# 01_-_LED_DRIVER.net
KiCad netlist of a schematic drawn in Altium Designer
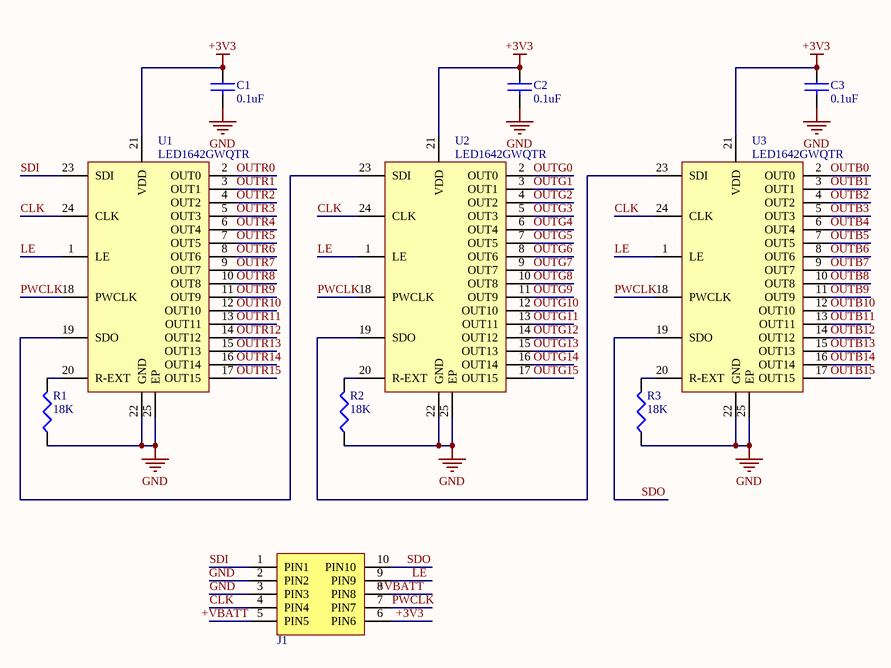
[diagram p0: [01] - LED DRIVER.SchDoc]

(export (version "E")
  (design (tool "Eeschema 10.0.6"))
  (components
    (comp (ref "C1")
      (value "0.1uF")
      (footprint "C0402")
      (description "Cap Ceramic 0.1uF 16V X7R 10% SMD 0402 125C C/T")
      (fields (field (name "TOLERANCE") "10%") (field (name "VOLTAGE") "16V"))
      (libsource (lib "Moon_Lamp_LED_Driver") (part "CL05B104KO5NNNC"))
    )
    (comp (ref "C2")
      (value "0.1uF")
      (footprint "C0402")
      (description "Cap Ceramic 0.1uF 16V X7R 10% SMD 0402 125C C/T")
      (fields (field (name "TOLERANCE") "10%") (field (name "VOLTAGE") "16V"))
      (libsource (lib "Moon_Lamp_LED_Driver") (part "CL05B104KO5NNNC"))
    )
    (comp (ref "C3")
      (value "0.1uF")
      (footprint "C0402")
      (description "Cap Ceramic 0.1uF 16V X7R 10% SMD 0402 125C C/T")
      (fields (field (name "TOLERANCE") "10%") (field (name "VOLTAGE") "16V"))
      (libsource (lib "Moon_Lamp_LED_Driver") (part "CL05B104KO5NNNC"))
    )
    (comp (ref "J1")
      (value "20021121-00010C4LF")
      (footprint "20021121-00010C4LF")
      (description "CONN HEADER SMD 10POS 1.27MM")
      (fields (field (name "MANUFACTURER") "Amphenol FCI"))
      (libsource (lib "Moon_Lamp_LED_Driver") (part "20021121-00010C4LF"))
    )
    (comp (ref "R1")
      (value "18K")
      (footprint "R0402")
      (fields
        (field (name "MANUFACTURER") "TE Connectivity")
        (field (name "MANUFACTURER PART NUMBER") "CRGCQ0402F18K")
      )
      (libsource (lib "Moon_Lamp_LED_Driver") (part "CRGCQ0402F18K"))
    )
    (comp (ref "R2")
      (value "18K")
      (footprint "R0402")
      (fields
        (field (name "MANUFACTURER") "TE Connectivity")
        (field (name "MANUFACTURER PART NUMBER") "CRGCQ0402F18K")
      )
      (libsource (lib "Moon_Lamp_LED_Driver") (part "CRGCQ0402F18K"))
    )
    (comp (ref "R3")
      (value "18K")
      (footprint "R0402")
      (fields
        (field (name "MANUFACTURER") "TE Connectivity")
        (field (name "MANUFACTURER PART NUMBER") "CRGCQ0402F18K")
      )
      (libsource (lib "Moon_Lamp_LED_Driver") (part "CRGCQ0402F18K"))
    )
    (comp (ref "U1")
      (value "LED1642GWQTR")
      (footprint "QFN24")
      (description "IC LED DRIVER LIN DIM 40MA 24QFN")
      (fields (field (name "MANUFACTURER") "STMicroelectronics"))
      (libsource (lib "Moon_Lamp_LED_Driver") (part "LED1642GWQTR"))
    )
    (comp (ref "U2")
      (value "LED1642GWQTR")
      (footprint "QFN24")
      (description "IC LED DRIVER LIN DIM 40MA 24QFN")
      (fields (field (name "MANUFACTURER") "STMicroelectronics"))
      (libsource (lib "Moon_Lamp_LED_Driver") (part "LED1642GWQTR"))
    )
    (comp (ref "U3")
      (value "LED1642GWQTR")
      (footprint "QFN24")
      (description "IC LED DRIVER LIN DIM 40MA 24QFN")
      (fields (field (name "MANUFACTURER") "STMicroelectronics"))
      (libsource (lib "Moon_Lamp_LED_Driver") (part "LED1642GWQTR"))
    )
  )
  (nets
    (net (code "1") (name "+3V3") (class "Default")
      (node (ref "C1") (pin "1") (pinfunction "1_1") (pintype "passive"))
      (node (ref "C2") (pin "1") (pinfunction "1_1") (pintype "passive"))
      (node (ref "C3") (pin "1") (pinfunction "1_1") (pintype "passive"))
      (node (ref "J1") (pin "6") (pinfunction "PIN6_6") (pintype "power_in"))
      (node (ref "U1") (pin "21") (pinfunction "VDD_21") (pintype "passive"))
      (node (ref "U2") (pin "21") (pinfunction "VDD_21") (pintype "passive"))
      (node (ref "U3") (pin "21") (pinfunction "VDD_21") (pintype "passive"))
    )
    (net (code "2") (name "/+VBATT") (class "Default")
      (node (ref "J1") (pin "5") (pinfunction "PIN5_5") (pintype "power_in"))
      (node (ref "J1") (pin "8") (pinfunction "PIN8_8") (pintype "power_in"))
    )
    (net (code "3") (name "/CLK") (class "Default")
      (node (ref "J1") (pin "4") (pinfunction "PIN4_4") (pintype "power_in"))
      (node (ref "U1") (pin "24") (pinfunction "CLK_24") (pintype "passive"))
      (node (ref "U2") (pin "24") (pinfunction "CLK_24") (pintype "passive"))
      (node (ref "U3") (pin "24") (pinfunction "CLK_24") (pintype "passive"))
    )
    (net (code "4") (name "/LE") (class "Default")
      (node (ref "J1") (pin "9") (pinfunction "PIN9_9") (pintype "power_in"))
      (node (ref "U1") (pin "1") (pinfunction "LE_1") (pintype "passive"))
      (node (ref "U2") (pin "1") (pinfunction "LE_1") (pintype "passive"))
      (node (ref "U3") (pin "1") (pinfunction "LE_1") (pintype "passive"))
    )
    (net (code "5") (name "/OUTB0") (class "Default")
      (node (ref "U3") (pin "2") (pinfunction "OUT0_2") (pintype "passive"))
    )
    (net (code "6") (name "/OUTB1") (class "Default")
      (node (ref "U3") (pin "3") (pinfunction "OUT1_3") (pintype "passive"))
    )
    (net (code "7") (name "/OUTB2") (class "Default")
      (node (ref "U3") (pin "4") (pinfunction "OUT2_4") (pintype "passive"))
    )
    (net (code "8") (name "/OUTB3") (class "Default")
      (node (ref "U3") (pin "5") (pinfunction "OUT3_5") (pintype "passive"))
    )
    (net (code "9") (name "/OUTB4") (class "Default")
      (node (ref "U3") (pin "6") (pinfunction "OUT4_6") (pintype "passive"))
    )
    (net (code "10") (name "/OUTB5") (class "Default")
      (node (ref "U3") (pin "7") (pinfunction "OUT5_7") (pintype "passive"))
    )
    (net (code "11") (name "/OUTB6") (class "Default")
      (node (ref "U3") (pin "8") (pinfunction "OUT6_8") (pintype "passive"))
    )
    (net (code "12") (name "/OUTB7") (class "Default")
      (node (ref "U3") (pin "9") (pinfunction "OUT7_9") (pintype "passive"))
    )
    (net (code "13") (name "/OUTB8") (class "Default")
      (node (ref "U3") (pin "10") (pinfunction "OUT8_10") (pintype "passive"))
    )
    (net (code "14") (name "/OUTB9") (class "Default")
      (node (ref "U3") (pin "11") (pinfunction "OUT9_11") (pintype "passive"))
    )
    (net (code "15") (name "/OUTB10") (class "Default")
      (node (ref "U3") (pin "12") (pinfunction "OUT10_12") (pintype "passive"))
    )
    (net (code "16") (name "/OUTB11") (class "Default")
      (node (ref "U3") (pin "13") (pinfunction "OUT11_13") (pintype "passive"))
    )
    (net (code "17") (name "/OUTB12") (class "Default")
      (node (ref "U3") (pin "14") (pinfunction "OUT12_14") (pintype "passive"))
    )
    (net (code "18") (name "/OUTB13") (class "Default")
      (node (ref "U3") (pin "15") (pinfunction "OUT13_15") (pintype "passive"))
    )
    (net (code "19") (name "/OUTB14") (class "Default")
      (node (ref "U3") (pin "16") (pinfunction "OUT14_16") (pintype "passive"))
    )
    (net (code "20") (name "/OUTB15") (class "Default")
      (node (ref "U3") (pin "17") (pinfunction "OUT15_17") (pintype "passive"))
    )
    (net (code "21") (name "/OUTG0") (class "Default")
      (node (ref "U2") (pin "2") (pinfunction "OUT0_2") (pintype "passive"))
    )
    (net (code "22") (name "/OUTG1") (class "Default")
      (node (ref "U2") (pin "3") (pinfunction "OUT1_3") (pintype "passive"))
    )
    (net (code "23") (name "/OUTG2") (class "Default")
      (node (ref "U2") (pin "4") (pinfunction "OUT2_4") (pintype "passive"))
    )
    (net (code "24") (name "/OUTG3") (class "Default")
      (node (ref "U2") (pin "5") (pinfunction "OUT3_5") (pintype "passive"))
    )
    (net (code "25") (name "/OUTG4") (class "Default")
      (node (ref "U2") (pin "6") (pinfunction "OUT4_6") (pintype "passive"))
    )
    (net (code "26") (name "/OUTG5") (class "Default")
      (node (ref "U2") (pin "7") (pinfunction "OUT5_7") (pintype "passive"))
    )
    (net (code "27") (name "/OUTG6") (class "Default")
      (node (ref "U2") (pin "8") (pinfunction "OUT6_8") (pintype "passive"))
    )
    (net (code "28") (name "/OUTG7") (class "Default")
      (node (ref "U2") (pin "9") (pinfunction "OUT7_9") (pintype "passive"))
    )
    (net (code "29") (name "/OUTG8") (class "Default")
      (node (ref "U2") (pin "10") (pinfunction "OUT8_10") (pintype "passive"))
    )
    (net (code "30") (name "/OUTG9") (class "Default")
      (node (ref "U2") (pin "11") (pinfunction "OUT9_11") (pintype "passive"))
    )
    (net (code "31") (name "/OUTG10") (class "Default")
      (node (ref "U2") (pin "12") (pinfunction "OUT10_12") (pintype "passive"))
    )
    (net (code "32") (name "/OUTG11") (class "Default")
      (node (ref "U2") (pin "13") (pinfunction "OUT11_13") (pintype "passive"))
    )
    (net (code "33") (name "/OUTG12") (class "Default")
      (node (ref "U2") (pin "14") (pinfunction "OUT12_14") (pintype "passive"))
    )
    (net (code "34") (name "/OUTG13") (class "Default")
      (node (ref "U2") (pin "15") (pinfunction "OUT13_15") (pintype "passive"))
    )
    (net (code "35") (name "/OUTG14") (class "Default")
      (node (ref "U2") (pin "16") (pinfunction "OUT14_16") (pintype "passive"))
    )
    (net (code "36") (name "/OUTG15") (class "Default")
      (node (ref "U2") (pin "17") (pinfunction "OUT15_17") (pintype "passive"))
    )
    (net (code "37") (name "/OUTR0") (class "Default")
      (node (ref "U1") (pin "2") (pinfunction "OUT0_2") (pintype "passive"))
    )
    (net (code "38") (name "/OUTR1") (class "Default")
      (node (ref "U1") (pin "3") (pinfunction "OUT1_3") (pintype "passive"))
    )
    (net (code "39") (name "/OUTR2") (class "Default")
      (node (ref "U1") (pin "4") (pinfunction "OUT2_4") (pintype "passive"))
    )
    (net (code "40") (name "/OUTR3") (class "Default")
      (node (ref "U1") (pin "5") (pinfunction "OUT3_5") (pintype "passive"))
    )
    (net (code "41") (name "/OUTR4") (class "Default")
      (node (ref "U1") (pin "6") (pinfunction "OUT4_6") (pintype "passive"))
    )
    (net (code "42") (name "/OUTR5") (class "Default")
      (node (ref "U1") (pin "7") (pinfunction "OUT5_7") (pintype "passive"))
    )
    (net (code "43") (name "/OUTR6") (class "Default")
      (node (ref "U1") (pin "8") (pinfunction "OUT6_8") (pintype "passive"))
    )
    (net (code "44") (name "/OUTR7") (class "Default")
      (node (ref "U1") (pin "9") (pinfunction "OUT7_9") (pintype "passive"))
    )
    (net (code "45") (name "/OUTR8") (class "Default")
      (node (ref "U1") (pin "10") (pinfunction "OUT8_10") (pintype "passive"))
    )
    (net (code "46") (name "/OUTR9") (class "Default")
      (node (ref "U1") (pin "11") (pinfunction "OUT9_11") (pintype "passive"))
    )
    (net (code "47") (name "/OUTR10") (class "Default")
      (node (ref "U1") (pin "12") (pinfunction "OUT10_12") (pintype "passive"))
    )
    (net (code "48") (name "/OUTR11") (class "Default")
      (node (ref "U1") (pin "13") (pinfunction "OUT11_13") (pintype "passive"))
    )
    (net (code "49") (name "/OUTR12") (class "Default")
      (node (ref "U1") (pin "14") (pinfunction "OUT12_14") (pintype "passive"))
    )
    (net (code "50") (name "/OUTR13") (class "Default")
      (node (ref "U1") (pin "15") (pinfunction "OUT13_15") (pintype "passive"))
    )
    (net (code "51") (name "/OUTR14") (class "Default")
      (node (ref "U1") (pin "16") (pinfunction "OUT14_16") (pintype "passive"))
    )
    (net (code "52") (name "/OUTR15") (class "Default")
      (node (ref "U1") (pin "17") (pinfunction "OUT15_17") (pintype "passive"))
    )
    (net (code "53") (name "/PWCLK") (class "Default")
      (node (ref "J1") (pin "7") (pinfunction "PIN7_7") (pintype "power_in"))
      (node (ref "U1") (pin "18") (pinfunction "PWCLK_18") (pintype "passive"))
      (node (ref "U2") (pin "18") (pinfunction "PWCLK_18") (pintype "passive"))
      (node (ref "U3") (pin "18") (pinfunction "PWCLK_18") (pintype "passive"))
    )
    (net (code "54") (name "/SDI") (class "Default")
      (node (ref "J1") (pin "1") (pinfunction "PIN1_1") (pintype "power_in"))
      (node (ref "U1") (pin "23") (pinfunction "SDI_23") (pintype "passive"))
    )
    (net (code "55") (name "/SDO") (class "Default")
      (node (ref "J1") (pin "10") (pinfunction "PIN10_10") (pintype "power_in"))
      (node (ref "U3") (pin "19") (pinfunction "SDO_19") (pintype "passive"))
    )
    (net (code "56") (name "GND") (class "Default")
      (node (ref "C1") (pin "2") (pinfunction "2_2") (pintype "passive"))
      (node (ref "C2") (pin "2") (pinfunction "2_2") (pintype "passive"))
      (node (ref "C3") (pin "2") (pinfunction "2_2") (pintype "passive"))
      (node (ref "J1") (pin "2") (pinfunction "PIN2_2") (pintype "power_in"))
      (node (ref "J1") (pin "3") (pinfunction "PIN3_3") (pintype "power_in"))
      (node (ref "R1") (pin "1") (pinfunction "1_1") (pintype "passive"))
      (node (ref "R2") (pin "1") (pinfunction "1_1") (pintype "passive"))
      (node (ref "R3") (pin "1") (pinfunction "1_1") (pintype "passive"))
      (node (ref "U1") (pin "22") (pinfunction "GND_22") (pintype "passive"))
      (node (ref "U1") (pin "25") (pinfunction "EP_25") (pintype "passive"))
      (node (ref "U2") (pin "22") (pinfunction "GND_22") (pintype "passive"))
      (node (ref "U2") (pin "25") (pinfunction "EP_25") (pintype "passive"))
      (node (ref "U3") (pin "22") (pinfunction "GND_22") (pintype "passive"))
      (node (ref "U3") (pin "25") (pinfunction "EP_25") (pintype "passive"))
    )
    (net (code "57") (name "Net-(U1-R-EXT)") (class "Default")
      (node (ref "R1") (pin "2") (pinfunction "2_2") (pintype "passive"))
      (node (ref "U1") (pin "20") (pinfunction "R-EXT_20") (pintype "passive"))
    )
    (net (code "58") (name "Net-(U1-SDO)") (class "Default")
      (node (ref "U1") (pin "19") (pinfunction "SDO_19") (pintype "passive"))
      (node (ref "U2") (pin "23") (pinfunction "SDI_23") (pintype "passive"))
    )
    (net (code "59") (name "Net-(U2-R-EXT)") (class "Default")
      (node (ref "R2") (pin "2") (pinfunction "2_2") (pintype "passive"))
      (node (ref "U2") (pin "20") (pinfunction "R-EXT_20") (pintype "passive"))
    )
    (net (code "60") (name "Net-(U2-SDO)") (class "Default")
      (node (ref "U2") (pin "19") (pinfunction "SDO_19") (pintype "passive"))
      (node (ref "U3") (pin "23") (pinfunction "SDI_23") (pintype "passive"))
    )
    (net (code "61") (name "Net-(U3-R-EXT)") (class "Default")
      (node (ref "R3") (pin "2") (pinfunction "2_2") (pintype "passive"))
      (node (ref "U3") (pin "20") (pinfunction "R-EXT_20") (pintype "passive"))
    )
  )
)
